# LE910_eval_0.net
KiCad netlist of a schematic drawn in EAGLE
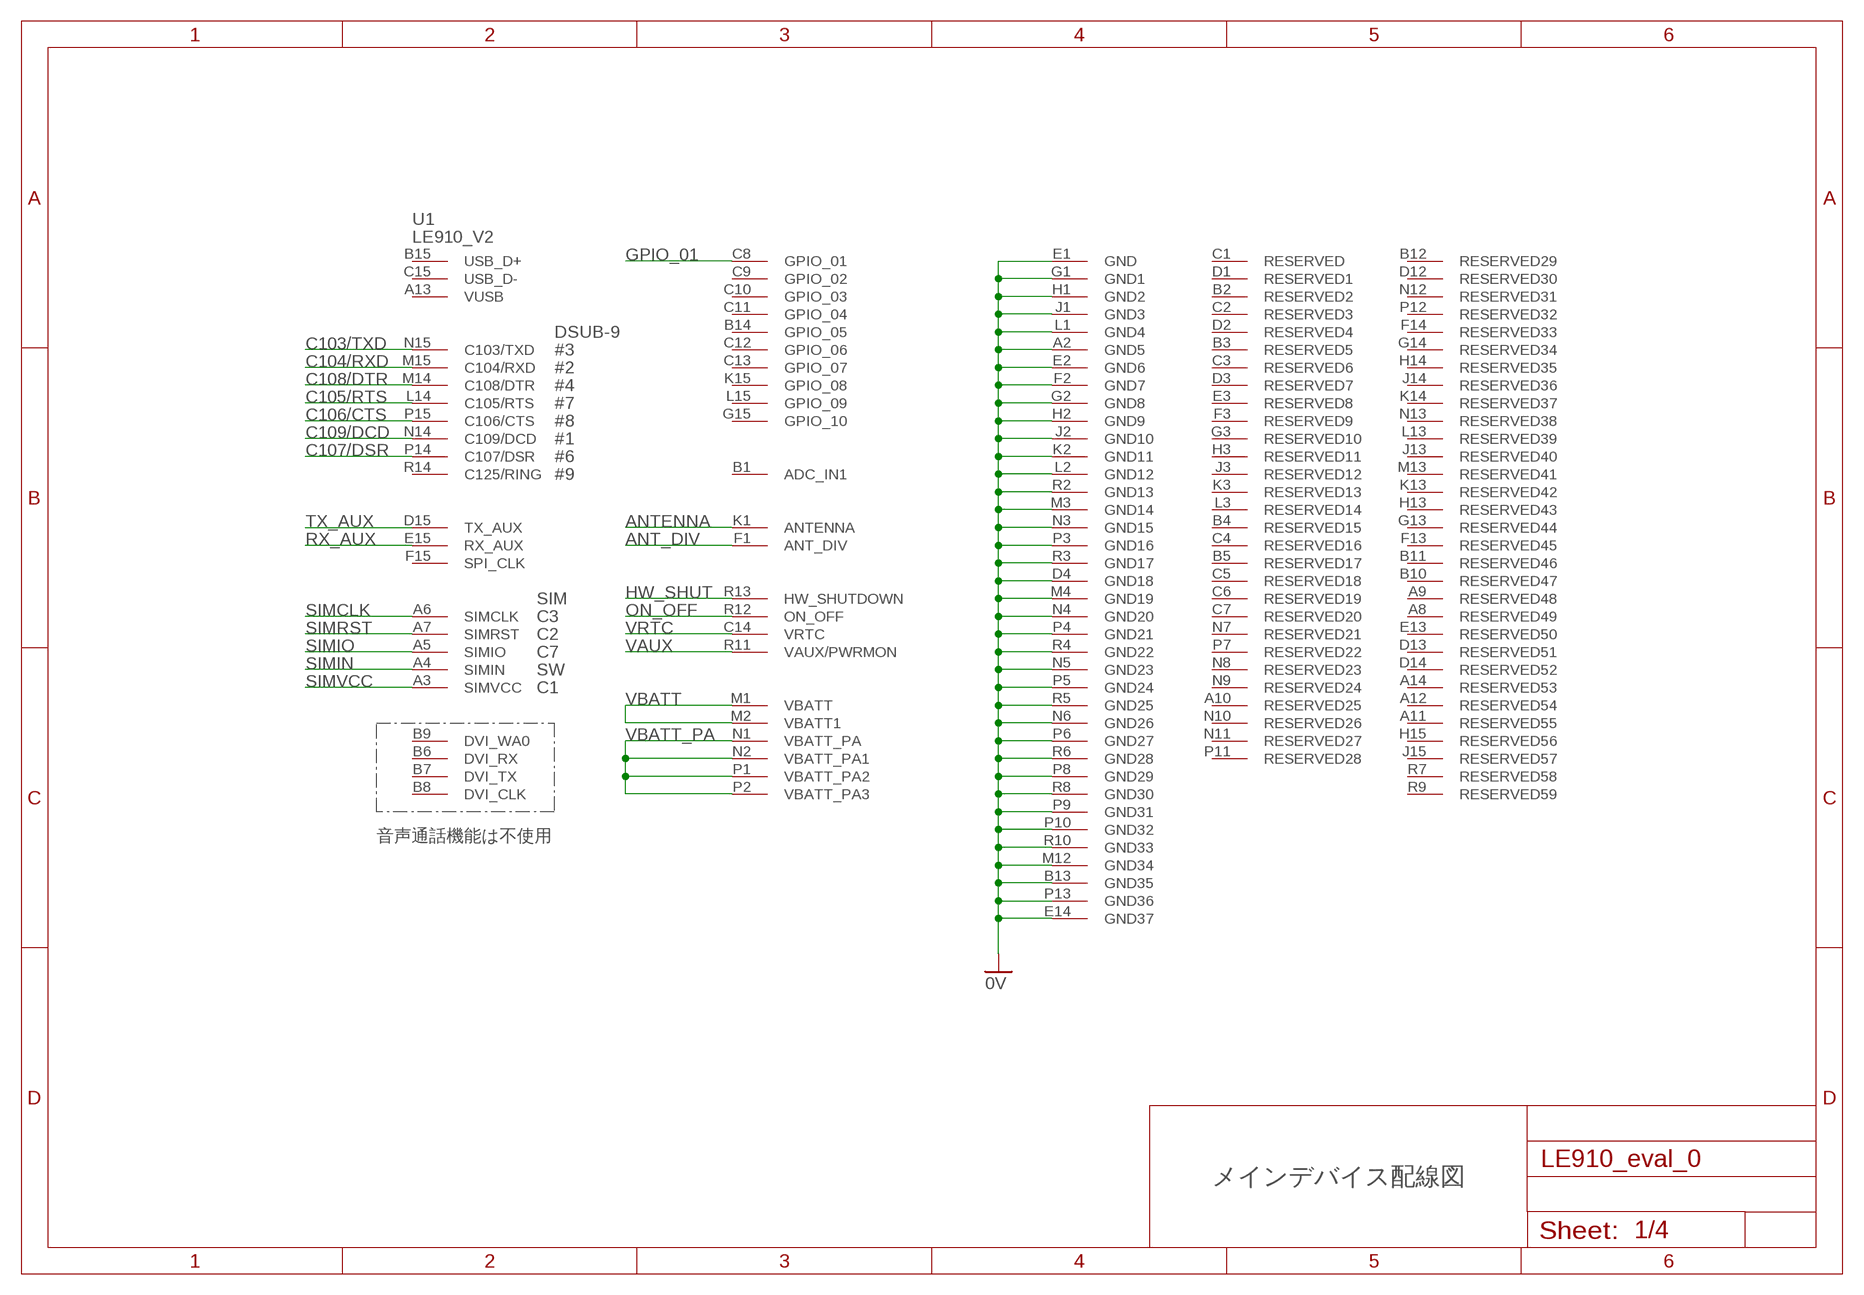
[diagram p0: schematic, sheet 1]
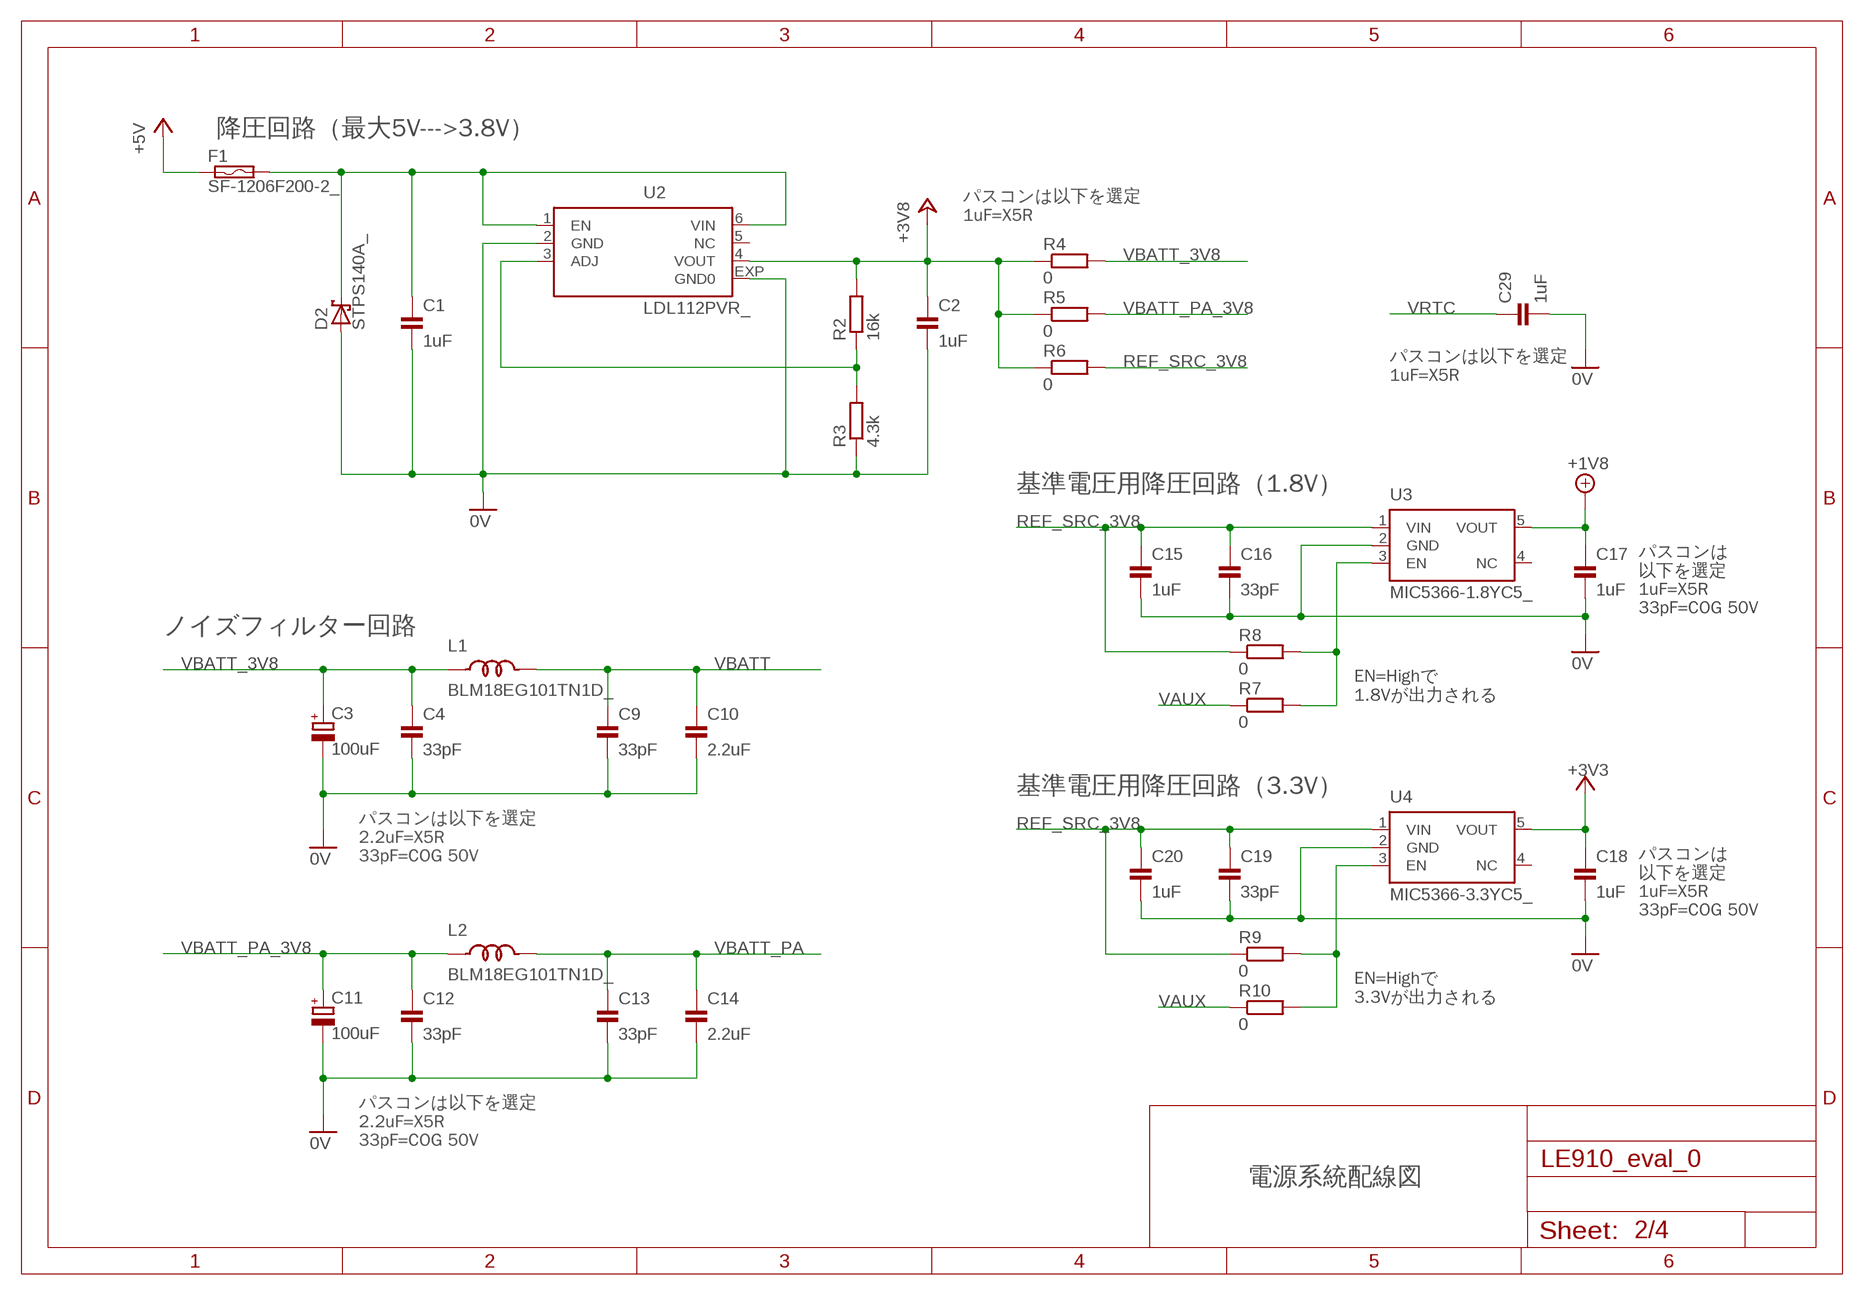
[diagram p1: schematic, sheet 2]
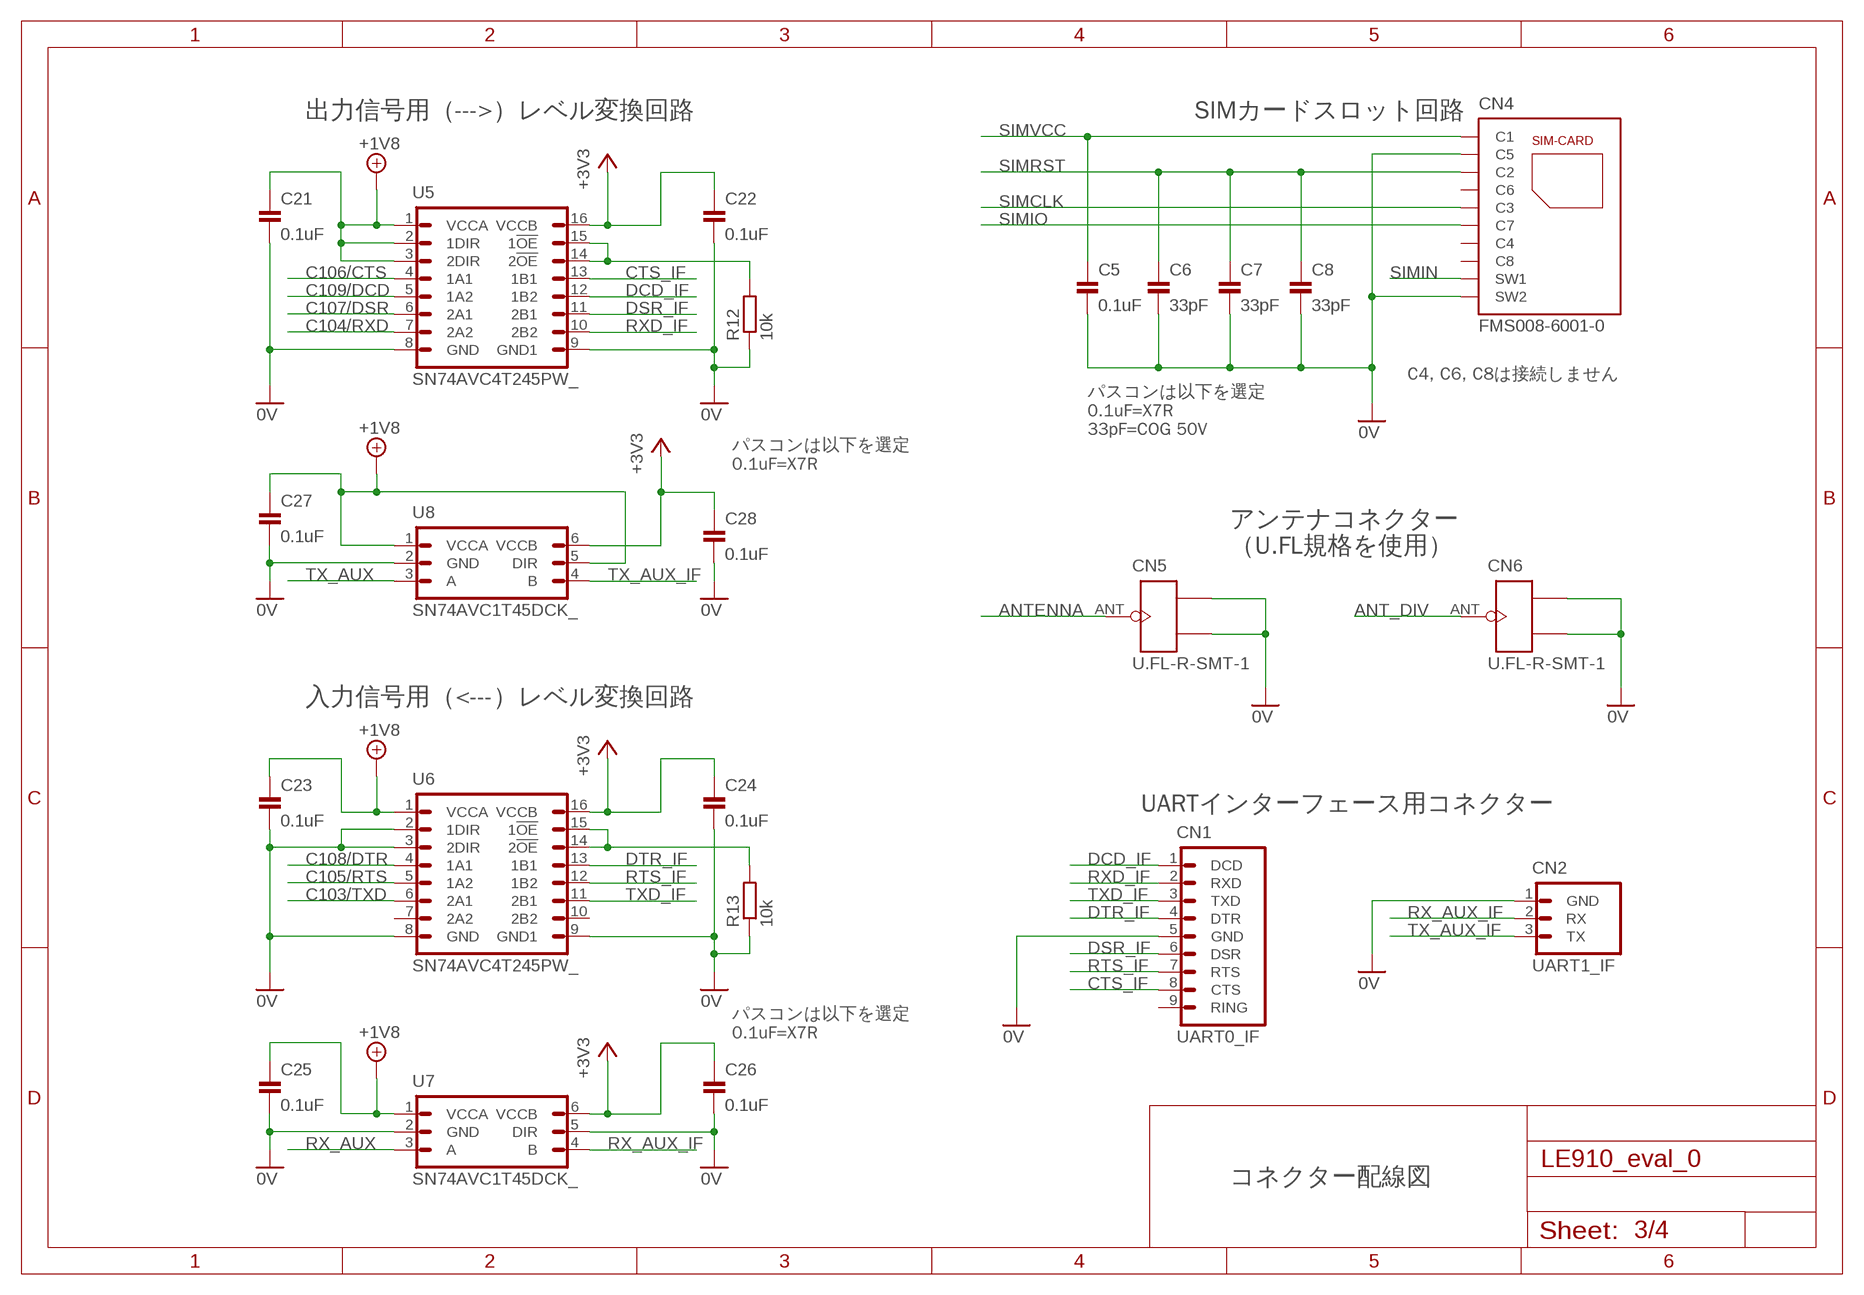
[diagram p2: schematic, sheet 3]
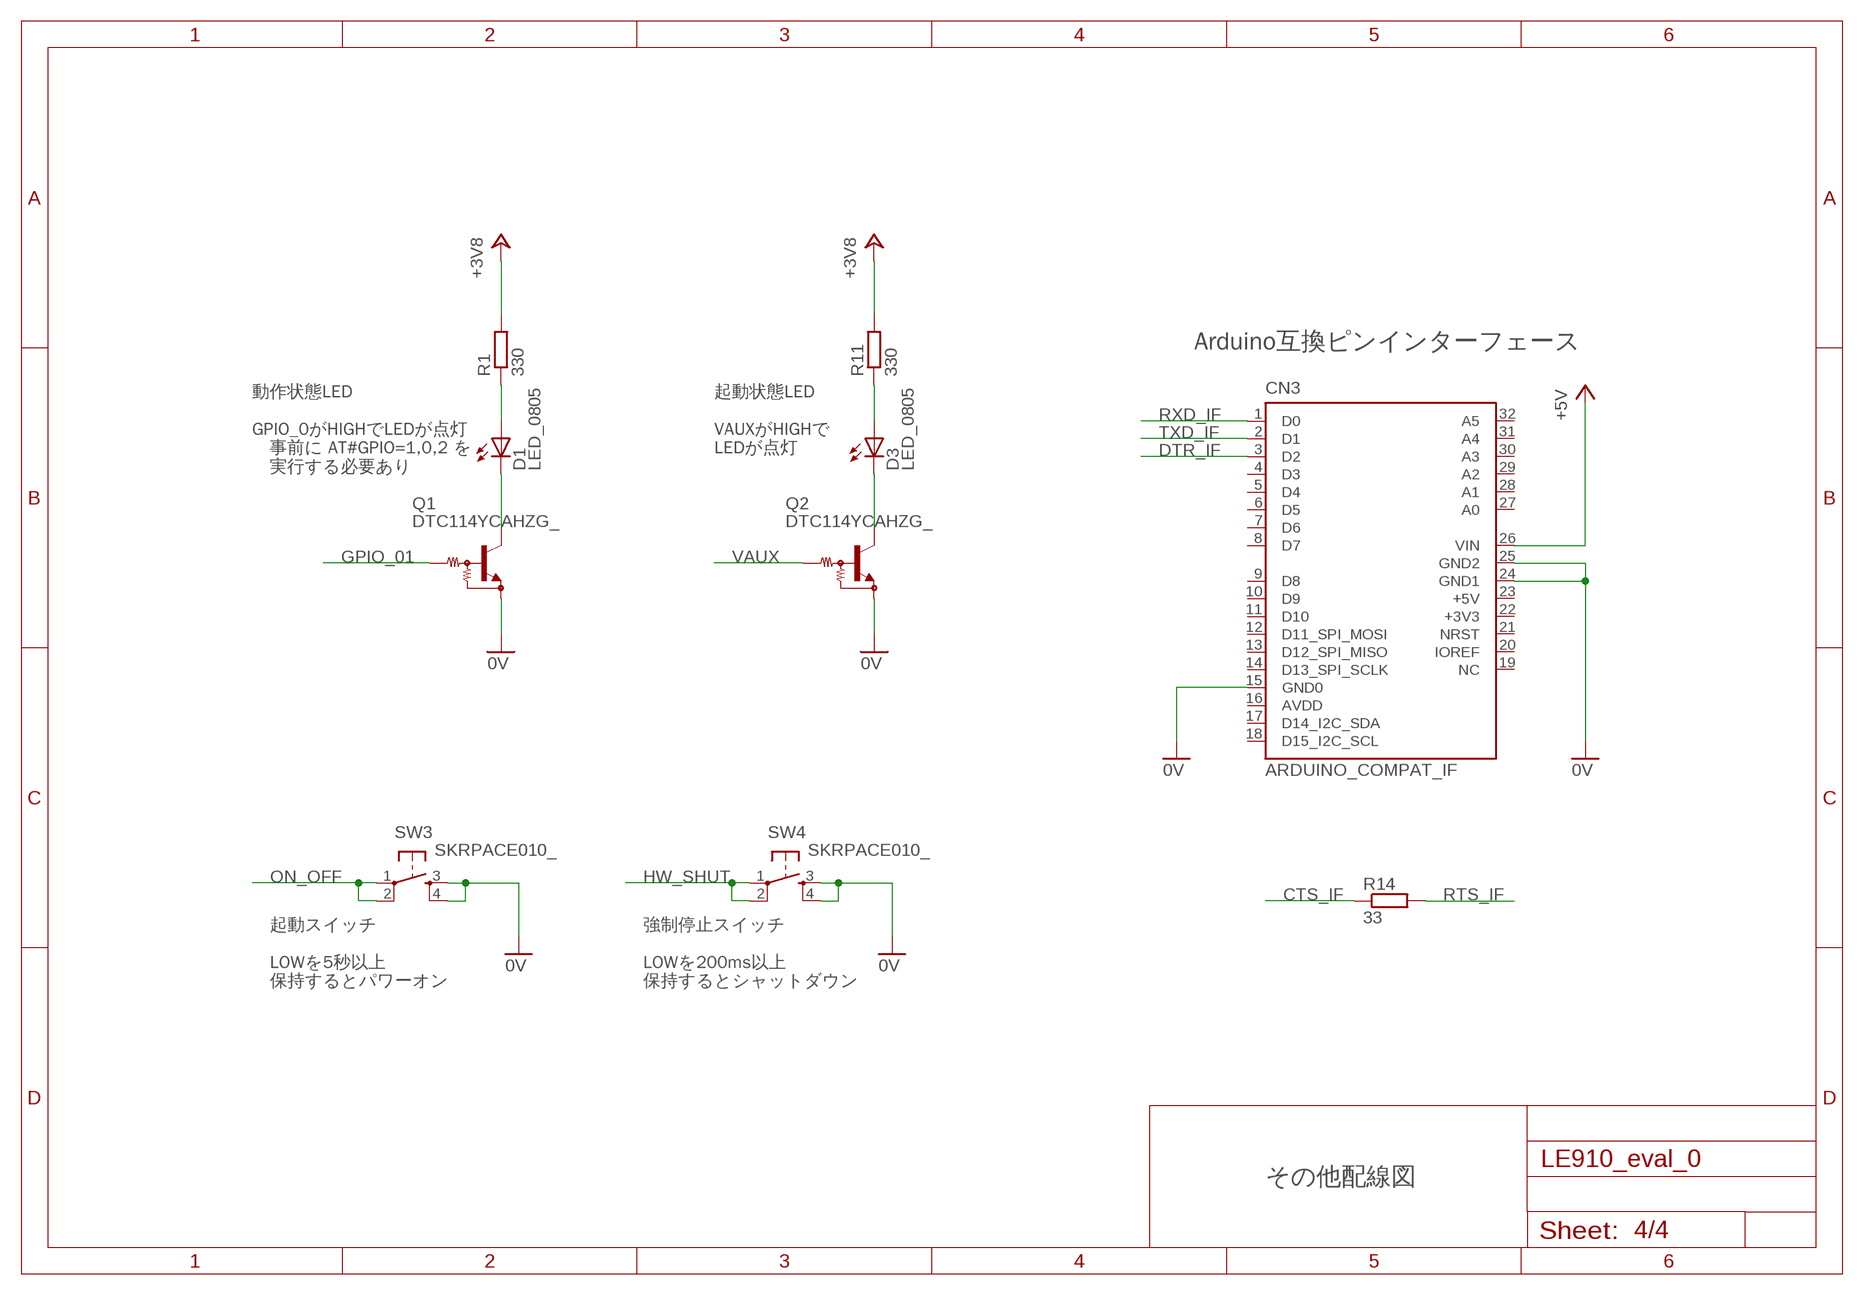
[diagram p3: schematic, sheet 4]

(export (version "E")
  (design (tool "Eeschema 10.0.6"))
  (components
    (comp (ref "CN3")
      (value "ARDUINO_COMPAT_IF")
      (footprint "eagle-import:ARDUINO_COMPAT_IF")
      (libsource (lib "eagle-import") (part "ARDUINO_COMPAT_IF"))
    )
    (comp (ref "D1")
      (value "LED_0805")
      (footprint "eagle-import:CHIPLED_0805")
      (libsource (lib "eagle-import") (part "LED_0805"))
    )
    (comp (ref "D3")
      (value "LED_0805")
      (footprint "eagle-import:CHIPLED_0805")
      (libsource (lib "eagle-import") (part "LED_0805"))
    )
    (comp (ref "Q1")
      (value "DTC114YCAHZG_")
      (footprint "eagle-import:SOT23_DEV")
      (libsource (lib "eagle-import") (part "DTC114YCAHZG_"))
    )
    (comp (ref "Q2")
      (value "DTC114YCAHZG_")
      (footprint "eagle-import:SOT23_DEV")
      (libsource (lib "eagle-import") (part "DTC114YCAHZG_"))
    )
    (comp (ref "R1")
      (value "330")
      (footprint "eagle-import:SMD_1608_DEV")
      (libsource (lib "eagle-import") (part "RESISTOR_0603_DEV"))
    )
    (comp (ref "R11")
      (value "330")
      (footprint "eagle-import:SMD_1608_DEV")
      (libsource (lib "eagle-import") (part "RESISTOR_0603_DEV"))
    )
    (comp (ref "R14")
      (value "33")
      (footprint "eagle-import:SMD_1608_DEV")
      (libsource (lib "eagle-import") (part "RESISTOR_0603_DEV"))
    )
    (comp (ref "SW3")
      (value "SKRPACE010_")
      (footprint "eagle-import:SKRPACE010_DEV")
      (libsource (lib "eagle-import") (part "SKRPACE010_"))
    )
    (comp (ref "SW4")
      (value "SKRPACE010_")
      (footprint "eagle-import:SKRPACE010_DEV")
      (libsource (lib "eagle-import") (part "SKRPACE010_"))
    )
    (comp (ref "C1")
      (value "1uF")
      (footprint "eagle-import:SMD_1608_DEV")
      (libsource (lib "eagle-import") (part "CAP_0603_DEV"))
    )
    (comp (ref "C2")
      (value "1uF")
      (footprint "eagle-import:SMD_1608_DEV")
      (libsource (lib "eagle-import") (part "CAP_0603_DEV"))
    )
    (comp (ref "C3")
      (value "100uF")
      (footprint "eagle-import:CT6032")
      (libsource (lib "eagle-import") (part "TPSW107K006R0150"))
    )
    (comp (ref "C4")
      (value "33pF")
      (footprint "eagle-import:SMD_1608_DEV")
      (libsource (lib "eagle-import") (part "CAP_0603_DEV"))
    )
    (comp (ref "C9")
      (value "33pF")
      (footprint "eagle-import:SMD_1608_DEV")
      (libsource (lib "eagle-import") (part "CAP_0603_DEV"))
    )
    (comp (ref "C10")
      (value "2.2uF")
      (footprint "eagle-import:SMD_1608_DEV")
      (libsource (lib "eagle-import") (part "CAP_0603_DEV"))
    )
    (comp (ref "C11")
      (value "100uF")
      (footprint "eagle-import:CT6032")
      (libsource (lib "eagle-import") (part "TPSW107K006R0150"))
    )
    (comp (ref "C12")
      (value "33pF")
      (footprint "eagle-import:SMD_1608_DEV")
      (libsource (lib "eagle-import") (part "CAP_0603_DEV"))
    )
    (comp (ref "C13")
      (value "33pF")
      (footprint "eagle-import:SMD_1608_DEV")
      (libsource (lib "eagle-import") (part "CAP_0603_DEV"))
    )
    (comp (ref "C14")
      (value "2.2uF")
      (footprint "eagle-import:SMD_1608_DEV")
      (libsource (lib "eagle-import") (part "CAP_0603_DEV"))
    )
    (comp (ref "C15")
      (value "1uF")
      (footprint "eagle-import:SMD_1608_DEV")
      (libsource (lib "eagle-import") (part "CAP_0603_DEV"))
    )
    (comp (ref "C16")
      (value "33pF")
      (footprint "eagle-import:SMD_1608_DEV")
      (libsource (lib "eagle-import") (part "CAP_0603_DEV"))
    )
    (comp (ref "C17")
      (value "1uF")
      (footprint "eagle-import:SMD_1608_DEV")
      (libsource (lib "eagle-import") (part "CAP_0603_DEV"))
    )
    (comp (ref "C18")
      (value "1uF")
      (footprint "eagle-import:SMD_1608_DEV")
      (libsource (lib "eagle-import") (part "CAP_0603_DEV"))
    )
    (comp (ref "C19")
      (value "33pF")
      (footprint "eagle-import:SMD_1608_DEV")
      (libsource (lib "eagle-import") (part "CAP_0603_DEV"))
    )
    (comp (ref "C20")
      (value "1uF")
      (footprint "eagle-import:SMD_1608_DEV")
      (libsource (lib "eagle-import") (part "CAP_0603_DEV"))
    )
    (comp (ref "C29")
      (value "1uF")
      (footprint "eagle-import:SMD_1608_DEV")
      (libsource (lib "eagle-import") (part "CAP_0603_DEV"))
    )
    (comp (ref "D2")
      (value "STPS140A_")
      (footprint "eagle-import:SMA_DEV")
      (libsource (lib "eagle-import") (part "STPS140A_"))
    )
    (comp (ref "F1")
      (value "SF-1206F200-2_")
      (footprint "eagle-import:SF-1206F_DEV")
      (libsource (lib "eagle-import") (part "SF-1206F200-2_"))
    )
    (comp (ref "L1")
      (value "BLM18EG101TN1D_")
      (footprint "eagle-import:SMD_1608_DEV")
      (libsource (lib "eagle-import") (part "BLM18EG101TN1D_"))
    )
    (comp (ref "L2")
      (value "BLM18EG101TN1D_")
      (footprint "eagle-import:SMD_1608_DEV")
      (libsource (lib "eagle-import") (part "BLM18EG101TN1D_"))
    )
    (comp (ref "R2")
      (value "16k")
      (footprint "eagle-import:SMD_1608_DEV")
      (libsource (lib "eagle-import") (part "RESISTOR_0603_DEV"))
    )
    (comp (ref "R3")
      (value "4.3k")
      (footprint "eagle-import:SMD_1608_DEV")
      (libsource (lib "eagle-import") (part "RESISTOR_0603_DEV"))
    )
    (comp (ref "R4")
      (value "0")
      (footprint "eagle-import:SMD_1608_DEV")
      (libsource (lib "eagle-import") (part "RESISTOR_0603_DEV"))
    )
    (comp (ref "R5")
      (value "0")
      (footprint "eagle-import:SMD_1608_DEV")
      (libsource (lib "eagle-import") (part "RESISTOR_0603_DEV"))
    )
    (comp (ref "R6")
      (value "0")
      (footprint "eagle-import:SMD_1608_DEV")
      (libsource (lib "eagle-import") (part "RESISTOR_0603_DEV"))
    )
    (comp (ref "R7")
      (value "0")
      (footprint "eagle-import:SMD_1608_DEV")
      (libsource (lib "eagle-import") (part "RESISTOR_0603_DEV"))
    )
    (comp (ref "R8")
      (value "0")
      (footprint "eagle-import:SMD_1608_DEV")
      (libsource (lib "eagle-import") (part "RESISTOR_0603_DEV"))
    )
    (comp (ref "R9")
      (value "0")
      (footprint "eagle-import:SMD_1608_DEV")
      (libsource (lib "eagle-import") (part "RESISTOR_0603_DEV"))
    )
    (comp (ref "R10")
      (value "0")
      (footprint "eagle-import:SMD_1608_DEV")
      (libsource (lib "eagle-import") (part "RESISTOR_0603_DEV"))
    )
    (comp (ref "U2")
      (value "LDL112PVR_")
      (footprint "eagle-import:DFN6-3X3_DEV")
      (libsource (lib "eagle-import") (part "LDL112PVR_"))
    )
    (comp (ref "U3")
      (value "MIC5366-1.8YC5_")
      (footprint "eagle-import:SC-70-5_DEV")
      (libsource (lib "eagle-import") (part "MIC5366-1.8YC5_"))
    )
    (comp (ref "U4")
      (value "MIC5366-3.3YC5_")
      (footprint "eagle-import:SC-70-5_DEV")
      (libsource (lib "eagle-import") (part "MIC5366-3.3YC5_"))
    )
    (comp (ref "U1")
      (value "LE910_V2")
      (footprint "eagle-import:LE910_V2")
      (libsource (lib "eagle-import") (part "LE910_V2"))
    )
    (comp (ref "C5")
      (value "0.1uF")
      (footprint "eagle-import:SMD_1608_DEV")
      (libsource (lib "eagle-import") (part "CAP_0603_DEV"))
    )
    (comp (ref "C6")
      (value "33pF")
      (footprint "eagle-import:SMD_1608_DEV")
      (libsource (lib "eagle-import") (part "CAP_0603_DEV"))
    )
    (comp (ref "C7")
      (value "33pF")
      (footprint "eagle-import:SMD_1608_DEV")
      (libsource (lib "eagle-import") (part "CAP_0603_DEV"))
    )
    (comp (ref "C8")
      (value "33pF")
      (footprint "eagle-import:SMD_1608_DEV")
      (libsource (lib "eagle-import") (part "CAP_0603_DEV"))
    )
    (comp (ref "C21")
      (value "0.1uF")
      (footprint "eagle-import:SMD_1608_DEV")
      (libsource (lib "eagle-import") (part "CAP_0603_DEV"))
    )
    (comp (ref "C22")
      (value "0.1uF")
      (footprint "eagle-import:SMD_1608_DEV")
      (libsource (lib "eagle-import") (part "CAP_0603_DEV"))
    )
    (comp (ref "C23")
      (value "0.1uF")
      (footprint "eagle-import:SMD_1608_DEV")
      (libsource (lib "eagle-import") (part "CAP_0603_DEV"))
    )
    (comp (ref "C24")
      (value "0.1uF")
      (footprint "eagle-import:SMD_1608_DEV")
      (libsource (lib "eagle-import") (part "CAP_0603_DEV"))
    )
    (comp (ref "C25")
      (value "0.1uF")
      (footprint "eagle-import:SMD_1608_DEV")
      (libsource (lib "eagle-import") (part "CAP_0603_DEV"))
    )
    (comp (ref "C26")
      (value "0.1uF")
      (footprint "eagle-import:SMD_1608_DEV")
      (libsource (lib "eagle-import") (part "CAP_0603_DEV"))
    )
    (comp (ref "C27")
      (value "0.1uF")
      (footprint "eagle-import:SMD_1608_DEV")
      (libsource (lib "eagle-import") (part "CAP_0603_DEV"))
    )
    (comp (ref "C28")
      (value "0.1uF")
      (footprint "eagle-import:SMD_1608_DEV")
      (libsource (lib "eagle-import") (part "CAP_0603_DEV"))
    )
    (comp (ref "CN1")
      (value "UART0_IF")
      (footprint "eagle-import:RS_232C_IF_9PIN")
      (libsource (lib "eagle-import") (part "RS_232C_IF"))
    )
    (comp (ref "CN2")
      (value "UART1_IF")
      (footprint "eagle-import:UART_IF_3PIN")
      (libsource (lib "eagle-import") (part "UART_IF"))
    )
    (comp (ref "CN4")
      (value "FMS008-6001-0")
      (footprint "eagle-import:FMS008-6001-0")
      (libsource (lib "eagle-import") (part "FMS008-6001-0"))
    )
    (comp (ref "CN5")
      (value "U.FL-R-SMT-1")
      (footprint "eagle-import:U.FL-R-SMT-1")
      (libsource (lib "eagle-import") (part "U.FL-R-SMT-1"))
    )
    (comp (ref "CN6")
      (value "U.FL-R-SMT-1")
      (footprint "eagle-import:U.FL-R-SMT-1")
      (libsource (lib "eagle-import") (part "U.FL-R-SMT-1"))
    )
    (comp (ref "R12")
      (value "10k")
      (footprint "eagle-import:SMD_1608_DEV")
      (libsource (lib "eagle-import") (part "RESISTOR_0603_DEV"))
    )
    (comp (ref "R13")
      (value "10k")
      (footprint "eagle-import:SMD_1608_DEV")
      (libsource (lib "eagle-import") (part "RESISTOR_0603_DEV"))
    )
    (comp (ref "U5")
      (value "SN74AVC4T245PW_")
      (footprint "eagle-import:TSSOP-16_DEV")
      (libsource (lib "eagle-import") (part "SN74AVC4T245PW_"))
    )
    (comp (ref "U6")
      (value "SN74AVC4T245PW_")
      (footprint "eagle-import:TSSOP-16_DEV")
      (libsource (lib "eagle-import") (part "SN74AVC4T245PW_"))
    )
    (comp (ref "U7")
      (value "SN74AVC1T45DCK_")
      (footprint "eagle-import:SC-70-6_DEV")
      (libsource (lib "eagle-import") (part "SN74AVC1T45DCK_"))
    )
    (comp (ref "U8")
      (value "SN74AVC1T45DCK_")
      (footprint "eagle-import:SC-70-6_DEV")
      (libsource (lib "eagle-import") (part "SN74AVC1T45DCK_"))
    )
  )
  (nets
    (net (code "1") (name "+1V8") (class "Default")
      (node (ref "C17") (pin "1") (pinfunction "1_1") (pintype "passive"))
      (node (ref "C21") (pin "1") (pinfunction "1_1") (pintype "passive"))
      (node (ref "C23") (pin "1") (pinfunction "1_1") (pintype "passive"))
      (node (ref "C25") (pin "1") (pinfunction "1_1") (pintype "passive"))
      (node (ref "C27") (pin "1") (pinfunction "1_1") (pintype "passive"))
      (node (ref "U3") (pin "5") (pinfunction "VOUT_5") (pintype "passive"))
      (node (ref "U5") (pin "1") (pinfunction "VCCA_1") (pintype "passive"))
      (node (ref "U5") (pin "2") (pinfunction "1DIR_2") (pintype "bidirectional"))
      (node (ref "U5") (pin "3") (pinfunction "2DIR_3") (pintype "bidirectional"))
      (node (ref "U6") (pin "1") (pinfunction "VCCA_1") (pintype "passive"))
      (node (ref "U7") (pin "1") (pinfunction "VCCA_1") (pintype "passive"))
      (node (ref "U8") (pin "1") (pinfunction "VCCA_1") (pintype "passive"))
      (node (ref "U8") (pin "5") (pinfunction "DIR_5") (pintype "bidirectional"))
    )
    (net (code "2") (name "+3V3") (class "Default")
      (node (ref "C18") (pin "1") (pinfunction "1_1") (pintype "passive"))
      (node (ref "C22") (pin "1") (pinfunction "1_1") (pintype "passive"))
      (node (ref "C24") (pin "1") (pinfunction "1_1") (pintype "passive"))
      (node (ref "C26") (pin "1") (pinfunction "1_1") (pintype "passive"))
      (node (ref "C28") (pin "1") (pinfunction "1_1") (pintype "passive"))
      (node (ref "U4") (pin "5") (pinfunction "VOUT_5") (pintype "passive"))
      (node (ref "U5") (pin "16") (pinfunction "VCCB_16") (pintype "passive"))
      (node (ref "U6") (pin "16") (pinfunction "VCCB_16") (pintype "passive"))
      (node (ref "U7") (pin "6") (pinfunction "VCCB_6") (pintype "passive"))
      (node (ref "U8") (pin "6") (pinfunction "VCCB_6") (pintype "passive"))
    )
    (net (code "3") (name "+3V8") (class "Default")
      (node (ref "C2") (pin "1") (pinfunction "1_1") (pintype "passive"))
      (node (ref "R1") (pin "2") (pinfunction "2_2") (pintype "passive"))
      (node (ref "R11") (pin "2") (pinfunction "2_2") (pintype "passive"))
      (node (ref "R2") (pin "2") (pinfunction "2_2") (pintype "passive"))
      (node (ref "R4") (pin "1") (pinfunction "1_1") (pintype "passive"))
      (node (ref "R5") (pin "1") (pinfunction "1_1") (pintype "passive"))
      (node (ref "R6") (pin "1") (pinfunction "1_1") (pintype "passive"))
      (node (ref "U2") (pin "4") (pinfunction "VOUT_4") (pintype "passive"))
    )
    (net (code "4") (name "+5V") (class "Default")
      (node (ref "CN3") (pin "26") (pinfunction "VIN_26") (pintype "passive"))
      (node (ref "F1") (pin "1") (pinfunction "1_1") (pintype "passive"))
    )
    (net (code "5") (name "0V") (class "Default")
      (node (ref "C1") (pin "2") (pinfunction "2_2") (pintype "passive"))
      (node (ref "C10") (pin "2") (pinfunction "2_2") (pintype "passive"))
      (node (ref "C11") (pin "-") (pinfunction "-_-") (pintype "passive"))
      (node (ref "C12") (pin "2") (pinfunction "2_2") (pintype "passive"))
      (node (ref "C13") (pin "2") (pinfunction "2_2") (pintype "passive"))
      (node (ref "C14") (pin "2") (pinfunction "2_2") (pintype "passive"))
      (node (ref "C15") (pin "2") (pinfunction "2_2") (pintype "passive"))
      (node (ref "C16") (pin "2") (pinfunction "2_2") (pintype "passive"))
      (node (ref "C17") (pin "2") (pinfunction "2_2") (pintype "passive"))
      (node (ref "C18") (pin "2") (pinfunction "2_2") (pintype "passive"))
      (node (ref "C19") (pin "2") (pinfunction "2_2") (pintype "passive"))
      (node (ref "C2") (pin "2") (pinfunction "2_2") (pintype "passive"))
      (node (ref "C20") (pin "2") (pinfunction "2_2") (pintype "passive"))
      (node (ref "C21") (pin "2") (pinfunction "2_2") (pintype "passive"))
      (node (ref "C22") (pin "2") (pinfunction "2_2") (pintype "passive"))
      (node (ref "C23") (pin "2") (pinfunction "2_2") (pintype "passive"))
      (node (ref "C24") (pin "2") (pinfunction "2_2") (pintype "passive"))
      (node (ref "C25") (pin "2") (pinfunction "2_2") (pintype "passive"))
      (node (ref "C26") (pin "2") (pinfunction "2_2") (pintype "passive"))
      (node (ref "C27") (pin "2") (pinfunction "2_2") (pintype "passive"))
      (node (ref "C28") (pin "2") (pinfunction "2_2") (pintype "passive"))
      (node (ref "C29") (pin "2") (pinfunction "2_2") (pintype "passive"))
      (node (ref "C3") (pin "-") (pinfunction "-_-") (pintype "passive"))
      (node (ref "C4") (pin "2") (pinfunction "2_2") (pintype "passive"))
      (node (ref "C5") (pin "2") (pinfunction "2_2") (pintype "passive"))
      (node (ref "C6") (pin "2") (pinfunction "2_2") (pintype "passive"))
      (node (ref "C7") (pin "2") (pinfunction "2_2") (pintype "passive"))
      (node (ref "C8") (pin "2") (pinfunction "2_2") (pintype "passive"))
      (node (ref "C9") (pin "2") (pinfunction "2_2") (pintype "passive"))
      (node (ref "CN1") (pin "5") (pinfunction "GND_5") (pintype "passive"))
      (node (ref "CN2") (pin "1") (pinfunction "GND_1") (pintype "passive"))
      (node (ref "CN3") (pin "15") (pinfunction "GND0_15") (pintype "passive"))
      (node (ref "CN3") (pin "24") (pinfunction "GND1_24") (pintype "passive"))
      (node (ref "CN3") (pin "25") (pinfunction "GND2_25") (pintype "passive"))
      (node (ref "CN4") (pin "C5") (pinfunction "C5_C5") (pintype "passive"))
      (node (ref "CN4") (pin "SW2") (pinfunction "SW2_SW2") (pintype "bidirectional"))
      (node (ref "CN5") (pin "GND1") (pinfunction "GND1_GND1") (pintype "passive"))
      (node (ref "CN5") (pin "GND2") (pinfunction "GND2_GND2") (pintype "passive"))
      (node (ref "CN6") (pin "GND1") (pinfunction "GND1_GND1") (pintype "passive"))
      (node (ref "CN6") (pin "GND2") (pinfunction "GND2_GND2") (pintype "passive"))
      (node (ref "D2") (pin "2") (pinfunction "A_2") (pintype "passive"))
      (node (ref "Q1") (pin "2") (pinfunction "E_2") (pintype "passive"))
      (node (ref "Q2") (pin "2") (pinfunction "E_2") (pintype "passive"))
      (node (ref "R12") (pin "1") (pinfunction "1_1") (pintype "passive"))
      (node (ref "R13") (pin "1") (pinfunction "1_1") (pintype "passive"))
      (node (ref "R3") (pin "1") (pinfunction "1_1") (pintype "passive"))
      (node (ref "SW3") (pin "3") (pinfunction "S_3") (pintype "passive"))
      (node (ref "SW3") (pin "4") (pinfunction "S1_4") (pintype "passive"))
      (node (ref "SW4") (pin "3") (pinfunction "S_3") (pintype "passive"))
      (node (ref "SW4") (pin "4") (pinfunction "S1_4") (pintype "passive"))
      (node (ref "U1") (pin "A2") (pinfunction "GND5_A2") (pintype "passive"))
      (node (ref "U1") (pin "B13") (pinfunction "GND35_B13") (pintype "passive"))
      (node (ref "U1") (pin "D4") (pinfunction "GND18_D4") (pintype "passive"))
      (node (ref "U1") (pin "E1") (pinfunction "GND_E1") (pintype "passive"))
      (node (ref "U1") (pin "E14") (pinfunction "GND37_E14") (pintype "passive"))
      (node (ref "U1") (pin "E2") (pinfunction "GND6_E2") (pintype "passive"))
      (node (ref "U1") (pin "F2") (pinfunction "GND7_F2") (pintype "passive"))
      (node (ref "U1") (pin "G1") (pinfunction "GND1_G1") (pintype "passive"))
      (node (ref "U1") (pin "G2") (pinfunction "GND8_G2") (pintype "passive"))
      (node (ref "U1") (pin "H1") (pinfunction "GND2_H1") (pintype "passive"))
      (node (ref "U1") (pin "H2") (pinfunction "GND9_H2") (pintype "passive"))
      (node (ref "U1") (pin "J1") (pinfunction "GND3_J1") (pintype "passive"))
      (node (ref "U1") (pin "J2") (pinfunction "GND10_J2") (pintype "passive"))
      (node (ref "U1") (pin "K2") (pinfunction "GND11_K2") (pintype "passive"))
      (node (ref "U1") (pin "L1") (pinfunction "GND4_L1") (pintype "passive"))
      (node (ref "U1") (pin "L2") (pinfunction "GND12_L2") (pintype "passive"))
      (node (ref "U1") (pin "M12") (pinfunction "GND34_M12") (pintype "passive"))
      (node (ref "U1") (pin "M3") (pinfunction "GND14_M3") (pintype "passive"))
      (node (ref "U1") (pin "M4") (pinfunction "GND19_M4") (pintype "passive"))
      (node (ref "U1") (pin "N3") (pinfunction "GND15_N3") (pintype "passive"))
      (node (ref "U1") (pin "N4") (pinfunction "GND20_N4") (pintype "passive"))
      (node (ref "U1") (pin "N5") (pinfunction "GND23_N5") (pintype "passive"))
      (node (ref "U1") (pin "N6") (pinfunction "GND26_N6") (pintype "passive"))
      (node (ref "U1") (pin "P10") (pinfunction "GND32_P10") (pintype "passive"))
      (node (ref "U1") (pin "P13") (pinfunction "GND36_P13") (pintype "passive"))
      (node (ref "U1") (pin "P3") (pinfunction "GND16_P3") (pintype "passive"))
      (node (ref "U1") (pin "P4") (pinfunction "GND21_P4") (pintype "passive"))
      (node (ref "U1") (pin "P5") (pinfunction "GND24_P5") (pintype "passive"))
      (node (ref "U1") (pin "P6") (pinfunction "GND27_P6") (pintype "passive"))
      (node (ref "U1") (pin "P8") (pinfunction "GND29_P8") (pintype "passive"))
      (node (ref "U1") (pin "P9") (pinfunction "GND31_P9") (pintype "passive"))
      (node (ref "U1") (pin "R10") (pinfunction "GND33_R10") (pintype "passive"))
      (node (ref "U1") (pin "R2") (pinfunction "GND13_R2") (pintype "passive"))
      (node (ref "U1") (pin "R3") (pinfunction "GND17_R3") (pintype "passive"))
      (node (ref "U1") (pin "R4") (pinfunction "GND22_R4") (pintype "passive"))
      (node (ref "U1") (pin "R5") (pinfunction "GND25_R5") (pintype "passive"))
      (node (ref "U1") (pin "R6") (pinfunction "GND28_R6") (pintype "passive"))
      (node (ref "U1") (pin "R8") (pinfunction "GND30_R8") (pintype "passive"))
      (node (ref "U2") (pin "2") (pinfunction "GND_2") (pintype "passive"))
      (node (ref "U2") (pin "EXP") (pinfunction "GND0_EXP") (pintype "passive"))
      (node (ref "U3") (pin "2") (pinfunction "GND_2") (pintype "passive"))
      (node (ref "U4") (pin "2") (pinfunction "GND_2") (pintype "passive"))
      (node (ref "U5") (pin "8") (pinfunction "GND_8") (pintype "passive"))
      (node (ref "U5") (pin "9") (pinfunction "GND1_9") (pintype "passive"))
      (node (ref "U6") (pin "2") (pinfunction "1DIR_2") (pintype "bidirectional"))
      (node (ref "U6") (pin "3") (pinfunction "2DIR_3") (pintype "bidirectional"))
      (node (ref "U6") (pin "8") (pinfunction "GND_8") (pintype "passive"))
      (node (ref "U6") (pin "9") (pinfunction "GND1_9") (pintype "passive"))
      (node (ref "U7") (pin "2") (pinfunction "GND_2") (pintype "passive"))
      (node (ref "U7") (pin "5") (pinfunction "DIR_5") (pintype "bidirectional"))
      (node (ref "U8") (pin "2") (pinfunction "GND_2") (pintype "passive"))
    )
    (net (code "6") (name "ANTENNA") (class "Default")
      (node (ref "CN5") (pin "ANT") (pinfunction "ANT_ANT") (pintype "passive"))
      (node (ref "U1") (pin "K1") (pinfunction "ANTENNA_K1") (pintype "bidirectional"))
    )
    (net (code "7") (name "ANT_DIV") (class "Default")
      (node (ref "CN6") (pin "ANT") (pinfunction "ANT_ANT") (pintype "passive"))
      (node (ref "U1") (pin "F1") (pinfunction "ANT_DIV_F1") (pintype "bidirectional"))
    )
    (net (code "8") (name "C103{slash}TXD") (class "Default")
      (node (ref "U1") (pin "N15") (pinfunction "C103/TXD_N15") (pintype "bidirectional"))
      (node (ref "U6") (pin "6") (pinfunction "2A1_6") (pintype "bidirectional"))
    )
    (net (code "9") (name "C104{slash}RXD") (class "Default")
      (node (ref "U1") (pin "M15") (pinfunction "C104/RXD_M15") (pintype "bidirectional"))
      (node (ref "U5") (pin "7") (pinfunction "2A2_7") (pintype "bidirectional"))
    )
    (net (code "10") (name "C105{slash}RTS") (class "Default")
      (node (ref "U1") (pin "L14") (pinfunction "C105/RTS_L14") (pintype "bidirectional"))
      (node (ref "U6") (pin "5") (pinfunction "1A2_5") (pintype "bidirectional"))
    )
    (net (code "11") (name "C106{slash}CTS") (class "Default")
      (node (ref "U1") (pin "P15") (pinfunction "C106/CTS_P15") (pintype "bidirectional"))
      (node (ref "U5") (pin "4") (pinfunction "1A1_4") (pintype "bidirectional"))
    )
    (net (code "12") (name "C107{slash}DSR") (class "Default")
      (node (ref "U1") (pin "P14") (pinfunction "C107/DSR_P14") (pintype "bidirectional"))
      (node (ref "U5") (pin "6") (pinfunction "2A1_6") (pintype "bidirectional"))
    )
    (net (code "13") (name "C108{slash}DTR") (class "Default")
      (node (ref "U1") (pin "M14") (pinfunction "C108/DTR_M14") (pintype "bidirectional"))
      (node (ref "U6") (pin "4") (pinfunction "1A1_4") (pintype "bidirectional"))
    )
    (net (code "14") (name "C109{slash}DCD") (class "Default")
      (node (ref "U1") (pin "N14") (pinfunction "C109/DCD_N14") (pintype "bidirectional"))
      (node (ref "U5") (pin "5") (pinfunction "1A2_5") (pintype "bidirectional"))
    )
    (net (code "15") (name "CTS_IF") (class "Default")
      (node (ref "CN1") (pin "8") (pinfunction "CTS_8") (pintype "bidirectional"))
      (node (ref "R14") (pin "1") (pinfunction "1_1") (pintype "passive"))
      (node (ref "U5") (pin "13") (pinfunction "1B1_13") (pintype "bidirectional"))
    )
    (net (code "16") (name "DCD_IF") (class "Default")
      (node (ref "CN1") (pin "1") (pinfunction "DCD_1") (pintype "bidirectional"))
      (node (ref "U5") (pin "12") (pinfunction "1B2_12") (pintype "bidirectional"))
    )
    (net (code "17") (name "DSR_IF") (class "Default")
      (node (ref "CN1") (pin "6") (pinfunction "DSR_6") (pintype "bidirectional"))
      (node (ref "U5") (pin "11") (pinfunction "2B1_11") (pintype "bidirectional"))
    )
    (net (code "18") (name "DTR_IF") (class "Default")
      (node (ref "CN1") (pin "4") (pinfunction "DTR_4") (pintype "bidirectional"))
      (node (ref "CN3") (pin "3") (pinfunction "D2_3") (pintype "bidirectional"))
      (node (ref "U6") (pin "13") (pinfunction "1B1_13") (pintype "bidirectional"))
    )
    (net (code "19") (name "GPIO_01") (class "Default")
      (node (ref "Q1") (pin "1") (pinfunction "B_1") (pintype "passive"))
      (node (ref "U1") (pin "C8") (pinfunction "GPIO_01_C8") (pintype "bidirectional"))
    )
    (net (code "20") (name "HW_SHUT") (class "Default")
      (node (ref "SW4") (pin "1") (pinfunction "P_1") (pintype "passive"))
      (node (ref "SW4") (pin "2") (pinfunction "P1_2") (pintype "passive"))
      (node (ref "U1") (pin "R13") (pinfunction "HW_SHUTDOWN_R13") (pintype "bidirectional"))
    )
    (net (code "21") (name "Net-(D1-PadA)") (class "Default")
      (node (ref "D1") (pin "A") (pinfunction "A_A") (pintype "passive"))
      (node (ref "R1") (pin "1") (pinfunction "1_1") (pintype "passive"))
    )
    (net (code "22") (name "Net-(D2-C)") (class "Default")
      (node (ref "C1") (pin "1") (pinfunction "1_1") (pintype "passive"))
      (node (ref "D2") (pin "1") (pinfunction "C_1") (pintype "passive"))
      (node (ref "F1") (pin "2") (pinfunction "2_2") (pintype "passive"))
      (node (ref "U2") (pin "1") (pinfunction "EN_1") (pintype "bidirectional"))
      (node (ref "U2") (pin "6") (pinfunction "VIN_6") (pintype "passive"))
    )
    (net (code "23") (name "Net-(D3-PadA)") (class "Default")
      (node (ref "D3") (pin "A") (pinfunction "A_A") (pintype "passive"))
      (node (ref "R11") (pin "1") (pinfunction "1_1") (pintype "passive"))
    )
    (net (code "24") (name "Net-(Q1-C)") (class "Default")
      (node (ref "D1") (pin "C") (pinfunction "C_C") (pintype "passive"))
      (node (ref "Q1") (pin "3") (pinfunction "C_3") (pintype "passive"))
    )
    (net (code "25") (name "Net-(Q2-C)") (class "Default")
      (node (ref "D3") (pin "C") (pinfunction "C_C") (pintype "passive"))
      (node (ref "Q2") (pin "3") (pinfunction "C_3") (pintype "passive"))
    )
    (net (code "26") (name "Net-(U2-ADJ)") (class "Default")
      (node (ref "R2") (pin "1") (pinfunction "1_1") (pintype "passive"))
      (node (ref "R3") (pin "2") (pinfunction "2_2") (pintype "passive"))
      (node (ref "U2") (pin "3") (pinfunction "ADJ_3") (pintype "bidirectional"))
    )
    (net (code "27") (name "Net-(U3-EN)") (class "Default")
      (node (ref "R7") (pin "2") (pinfunction "2_2") (pintype "passive"))
      (node (ref "R8") (pin "2") (pinfunction "2_2") (pintype "passive"))
      (node (ref "U3") (pin "3") (pinfunction "EN_3") (pintype "bidirectional"))
    )
    (net (code "28") (name "Net-(U4-EN)") (class "Default")
      (node (ref "R10") (pin "2") (pinfunction "2_2") (pintype "passive"))
      (node (ref "R9") (pin "2") (pinfunction "2_2") (pintype "passive"))
      (node (ref "U4") (pin "3") (pinfunction "EN_3") (pintype "bidirectional"))
    )
    (net (code "29") (name "Net-(U5-1~{OE})") (class "Default")
      (node (ref "R12") (pin "2") (pinfunction "2_2") (pintype "passive"))
      (node (ref "U5") (pin "14") (pinfunction "2~{OE}_14") (pintype "bidirectional"))
      (node (ref "U5") (pin "15") (pinfunction "1~{OE}_15") (pintype "bidirectional"))
    )
    (net (code "30") (name "Net-(U6-1~{OE})") (class "Default")
      (node (ref "R13") (pin "2") (pinfunction "2_2") (pintype "passive"))
      (node (ref "U6") (pin "14") (pinfunction "2~{OE}_14") (pintype "bidirectional"))
      (node (ref "U6") (pin "15") (pinfunction "1~{OE}_15") (pintype "bidirectional"))
    )
    (net (code "31") (name "ON_OFF") (class "Default")
      (node (ref "SW3") (pin "1") (pinfunction "P_1") (pintype "passive"))
      (node (ref "SW3") (pin "2") (pinfunction "P1_2") (pintype "passive"))
      (node (ref "U1") (pin "R12") (pinfunction "ON_OFF_R12") (pintype "bidirectional"))
    )
    (net (code "32") (name "REF_SRC_3V8") (class "Default")
      (node (ref "C15") (pin "1") (pinfunction "1_1") (pintype "passive"))
      (node (ref "C16") (pin "1") (pinfunction "1_1") (pintype "passive"))
      (node (ref "C19") (pin "1") (pinfunction "1_1") (pintype "passive"))
      (node (ref "C20") (pin "1") (pinfunction "1_1") (pintype "passive"))
      (node (ref "R6") (pin "2") (pinfunction "2_2") (pintype "passive"))
      (node (ref "R8") (pin "1") (pinfunction "1_1") (pintype "passive"))
      (node (ref "R9") (pin "1") (pinfunction "1_1") (pintype "passive"))
      (node (ref "U3") (pin "1") (pinfunction "VIN_1") (pintype "passive"))
      (node (ref "U4") (pin "1") (pinfunction "VIN_1") (pintype "passive"))
    )
    (net (code "33") (name "RTS_IF") (class "Default")
      (node (ref "CN1") (pin "7") (pinfunction "RTS_7") (pintype "bidirectional"))
      (node (ref "R14") (pin "2") (pinfunction "2_2") (pintype "passive"))
      (node (ref "U6") (pin "12") (pinfunction "1B2_12") (pintype "bidirectional"))
    )
    (net (code "34") (name "RXD_IF") (class "Default")
      (node (ref "CN1") (pin "2") (pinfunction "RXD_2") (pintype "bidirectional"))
      (node (ref "CN3") (pin "1") (pinfunction "D0_1") (pintype "bidirectional"))
      (node (ref "U5") (pin "10") (pinfunction "2B2_10") (pintype "bidirectional"))
    )
    (net (code "35") (name "RX_AUX") (class "Default")
      (node (ref "U1") (pin "E15") (pinfunction "RX_AUX_E15") (pintype "bidirectional"))
      (node (ref "U7") (pin "3") (pinfunction "A_3") (pintype "bidirectional"))
    )
    (net (code "36") (name "RX_AUX_IF") (class "Default")
      (node (ref "CN2") (pin "2") (pinfunction "RX_2") (pintype "bidirectional"))
      (node (ref "U7") (pin "4") (pinfunction "B_4") (pintype "bidirectional"))
    )
    (net (code "37") (name "SIMCLK") (class "Default")
      (node (ref "CN4") (pin "C3") (pinfunction "C3_C3") (pintype "bidirectional"))
      (node (ref "U1") (pin "A6") (pinfunction "SIMCLK_A6") (pintype "bidirectional"))
    )
    (net (code "38") (name "SIMIN") (class "Default")
      (node (ref "CN4") (pin "SW1") (pinfunction "SW1_SW1") (pintype "bidirectional"))
      (node (ref "U1") (pin "A4") (pinfunction "SIMIN_A4") (pintype "bidirectional"))
    )
    (net (code "39") (name "SIMIO") (class "Default")
      (node (ref "CN4") (pin "C7") (pinfunction "C7_C7") (pintype "bidirectional"))
      (node (ref "U1") (pin "A5") (pinfunction "SIMIO_A5") (pintype "bidirectional"))
    )
    (net (code "40") (name "SIMRST") (class "Default")
      (node (ref "C6") (pin "1") (pinfunction "1_1") (pintype "passive"))
      (node (ref "C7") (pin "1") (pinfunction "1_1") (pintype "passive"))
      (node (ref "C8") (pin "1") (pinfunction "1_1") (pintype "passive"))
      (node (ref "CN4") (pin "C2") (pinfunction "C2_C2") (pintype "bidirectional"))
      (node (ref "U1") (pin "A7") (pinfunction "SIMRST_A7") (pintype "bidirectional"))
    )
    (net (code "41") (name "SIMVCC") (class "Default")
      (node (ref "C5") (pin "1") (pinfunction "1_1") (pintype "passive"))
      (node (ref "CN4") (pin "C1") (pinfunction "C1_C1") (pintype "passive"))
      (node (ref "U1") (pin "A3") (pinfunction "SIMVCC_A3") (pintype "passive"))
    )
    (net (code "42") (name "TXD_IF") (class "Default")
      (node (ref "CN1") (pin "3") (pinfunction "TXD_3") (pintype "bidirectional"))
      (node (ref "CN3") (pin "2") (pinfunction "D1_2") (pintype "bidirectional"))
      (node (ref "U6") (pin "11") (pinfunction "2B1_11") (pintype "bidirectional"))
    )
    (net (code "43") (name "TX_AUX") (class "Default")
      (node (ref "U1") (pin "D15") (pinfunction "TX_AUX_D15") (pintype "bidirectional"))
      (node (ref "U8") (pin "3") (pinfunction "A_3") (pintype "bidirectional"))
    )
    (net (code "44") (name "TX_AUX_IF") (class "Default")
      (node (ref "CN2") (pin "3") (pinfunction "TX_3") (pintype "bidirectional"))
      (node (ref "U8") (pin "4") (pinfunction "B_4") (pintype "bidirectional"))
    )
    (net (code "45") (name "VAUX") (class "Default")
      (node (ref "Q2") (pin "1") (pinfunction "B_1") (pintype "passive"))
      (node (ref "R10") (pin "1") (pinfunction "1_1") (pintype "passive"))
      (node (ref "R7") (pin "1") (pinfunction "1_1") (pintype "passive"))
      (node (ref "U1") (pin "R11") (pinfunction "VAUX/PWRMON_R11") (pintype "bidirectional"))
    )
    (net (code "46") (name "VBATT") (class "Default")
      (node (ref "C10") (pin "1") (pinfunction "1_1") (pintype "passive"))
      (node (ref "C9") (pin "1") (pinfunction "1_1") (pintype "passive"))
      (node (ref "L1") (pin "2") (pinfunction "2_2") (pintype "passive"))
      (node (ref "U1") (pin "M1") (pinfunction "VBATT_M1") (pintype "passive"))
      (node (ref "U1") (pin "M2") (pinfunction "VBATT1_M2") (pintype "passive"))
    )
    (net (code "47") (name "VBATT_3V8") (class "Default")
      (node (ref "C3") (pin "+") (pinfunction "+_+") (pintype "passive"))
      (node (ref "C4") (pin "1") (pinfunction "1_1") (pintype "passive"))
      (node (ref "L1") (pin "1") (pinfunction "1_1") (pintype "passive"))
      (node (ref "R4") (pin "2") (pinfunction "2_2") (pintype "passive"))
    )
    (net (code "48") (name "VBATT_PA") (class "Default")
      (node (ref "C13") (pin "1") (pinfunction "1_1") (pintype "passive"))
      (node (ref "C14") (pin "1") (pinfunction "1_1") (pintype "passive"))
      (node (ref "L2") (pin "2") (pinfunction "2_2") (pintype "passive"))
      (node (ref "U1") (pin "N1") (pinfunction "VBATT_PA_N1") (pintype "passive"))
      (node (ref "U1") (pin "N2") (pinfunction "VBATT_PA1_N2") (pintype "passive"))
      (node (ref "U1") (pin "P1") (pinfunction "VBATT_PA2_P1") (pintype "passive"))
      (node (ref "U1") (pin "P2") (pinfunction "VBATT_PA3_P2") (pintype "passive"))
    )
    (net (code "49") (name "VBATT_PA_3V8") (class "Default")
      (node (ref "C11") (pin "+") (pinfunction "+_+") (pintype "passive"))
      (node (ref "C12") (pin "1") (pinfunction "1_1") (pintype "passive"))
      (node (ref "L2") (pin "1") (pinfunction "1_1") (pintype "passive"))
      (node (ref "R5") (pin "2") (pinfunction "2_2") (pintype "passive"))
    )
    (net (code "50") (name "VRTC") (class "Default")
      (node (ref "C29") (pin "1") (pinfunction "1_1") (pintype "passive"))
      (node (ref "U1") (pin "C14") (pinfunction "VRTC_C14") (pintype "bidirectional"))
    )
    (net (code "51") (name "unconnected-(CN1-RING-Pad9)") (class "Default")
      (node (ref "CN1") (pin "9") (pinfunction "RING_9") (pintype "bidirectional"))
    )
    (net (code "52") (name "unconnected-(CN3-+3V3-Pad22)") (class "Default")
      (node (ref "CN3") (pin "22") (pinfunction "+3V3_22") (pintype "passive"))
    )
    (net (code "53") (name "unconnected-(CN3-+5V-Pad23)") (class "Default")
      (node (ref "CN3") (pin "23") (pinfunction "+5V_23") (pintype "passive"))
    )
    (net (code "54") (name "unconnected-(CN3-A0-Pad27)") (class "Default")
      (node (ref "CN3") (pin "27") (pinfunction "A0_27") (pintype "bidirectional"))
    )
    (net (code "55") (name "unconnected-(CN3-A1-Pad28)") (class "Default")
      (node (ref "CN3") (pin "28") (pinfunction "A1_28") (pintype "bidirectional"))
    )
    (net (code "56") (name "unconnected-(CN3-A2-Pad29)") (class "Default")
      (node (ref "CN3") (pin "29") (pinfunction "A2_29") (pintype "bidirectional"))
    )
    (net (code "57") (name "unconnected-(CN3-A3-Pad30)") (class "Default")
      (node (ref "CN3") (pin "30") (pinfunction "A3_30") (pintype "bidirectional"))
    )
    (net (code "58") (name "unconnected-(CN3-A4-Pad31)") (class "Default")
      (node (ref "CN3") (pin "31") (pinfunction "A4_31") (pintype "bidirectional"))
    )
    (net (code "59") (name "unconnected-(CN3-A5-Pad32)") (class "Default")
      (node (ref "CN3") (pin "32") (pinfunction "A5_32") (pintype "bidirectional"))
    )
    (net (code "60") (name "unconnected-(CN3-AVDD-Pad16)") (class "Default")
      (node (ref "CN3") (pin "16") (pinfunction "AVDD_16") (pintype "passive"))
    )
    (net (code "61") (name "unconnected-(CN3-D3-Pad4)") (class "Default")
      (node (ref "CN3") (pin "4") (pinfunction "D3_4") (pintype "bidirectional"))
    )
    (net (code "62") (name "unconnected-(CN3-D4-Pad5)") (class "Default")
      (node (ref "CN3") (pin "5") (pinfunction "D4_5") (pintype "bidirectional"))
    )
    (net (code "63") (name "unconnected-(CN3-D5-Pad6)") (class "Default")
      (node (ref "CN3") (pin "6") (pinfunction "D5_6") (pintype "bidirectional"))
    )
    (net (code "64") (name "unconnected-(CN3-D6-Pad7)") (class "Default")
      (node (ref "CN3") (pin "7") (pinfunction "D6_7") (pintype "bidirectional"))
    )
    (net (code "65") (name "unconnected-(CN3-D7-Pad8)") (class "Default")
      (node (ref "CN3") (pin "8") (pinfunction "D7_8") (pintype "bidirectional"))
    )
    (net (code "66") (name "unconnected-(CN3-D8-Pad9)") (class "Default")
      (node (ref "CN3") (pin "9") (pinfunction "D8_9") (pintype "bidirectional"))
    )
    (net (code "67") (name "unconnected-(CN3-D9-Pad10)") (class "Default")
      (node (ref "CN3") (pin "10") (pinfunction "D9_10") (pintype "bidirectional"))
    )
    (net (code "68") (name "unconnected-(CN3-D10-Pad11)") (class "Default")
      (node (ref "CN3") (pin "11") (pinfunction "D10_11") (pintype "bidirectional"))
    )
    (net (code "69") (name "unconnected-(CN3-D11_SPI_MOSI-Pad12)") (class "Default")
      (node (ref "CN3") (pin "12") (pinfunction "D11_SPI_MOSI_12") (pintype "bidirectional"))
    )
    (net (code "70") (name "unconnected-(CN3-D12_SPI_MISO-Pad13)") (class "Default")
      (node (ref "CN3") (pin "13") (pinfunction "D12_SPI_MISO_13") (pintype "bidirectional"))
    )
    (net (code "71") (name "unconnected-(CN3-D13_SPI_SCLK-Pad14)") (class "Default")
      (node (ref "CN3") (pin "14") (pinfunction "D13_SPI_SCLK_14") (pintype "bidirectional"))
    )
    (net (code "72") (name "unconnected-(CN3-D14_I2C_SDA-Pad17)") (class "Default")
      (node (ref "CN3") (pin "17") (pinfunction "D14_I2C_SDA_17") (pintype "passive"))
    )
    (net (code "73") (name "unconnected-(CN3-D15_I2C_SCL-Pad18)") (class "Default")
      (node (ref "CN3") (pin "18") (pinfunction "D15_I2C_SCL_18") (pintype "passive"))
    )
    (net (code "74") (name "unconnected-(CN3-IOREF-Pad20)") (class "Default")
      (node (ref "CN3") (pin "20") (pinfunction "IOREF_20") (pintype "bidirectional"))
    )
    (net (code "75") (name "unconnected-(CN3-NC-Pad19)") (class "Default")
      (node (ref "CN3") (pin "19") (pinfunction "NC_19") (pintype "no_connect"))
    )
    (net (code "76") (name "unconnected-(CN3-NRST-Pad21)") (class "Default")
      (node (ref "CN3") (pin "21") (pinfunction "NRST_21") (pintype "bidirectional"))
    )
    (net (code "77") (name "unconnected-(CN4-PadC4)") (class "Default")
      (node (ref "CN4") (pin "C4") (pinfunction "C4_C4") (pintype "bidirectional"))
    )
    (net (code "78") (name "unconnected-(CN4-PadC6)") (class "Default")
      (node (ref "CN4") (pin "C6") (pinfunction "C6_C6") (pintype "passive"))
    )
    (net (code "79") (name "unconnected-(CN4-PadC8)") (class "Default")
      (node (ref "CN4") (pin "C8") (pinfunction "C8_C8") (pintype "bidirectional"))
    )
    (net (code "80") (name "unconnected-(U1-ADC_IN1-PadB1)") (class "Default")
      (node (ref "U1") (pin "B1") (pinfunction "ADC_IN1_B1") (pintype "bidirectional"))
    )
    (net (code "81") (name "unconnected-(U1-C125{slash}RING-PadR14)") (class "Default")
      (node (ref "U1") (pin "R14") (pinfunction "C125/RING_R14") (pintype "bidirectional"))
    )
    (net (code "82") (name "unconnected-(U1-DVI_CLK-PadB8)") (class "Default")
      (node (ref "U1") (pin "B8") (pinfunction "DVI_CLK_B8") (pintype "bidirectional"))
    )
    (net (code "83") (name "unconnected-(U1-DVI_RX-PadB6)") (class "Default")
      (node (ref "U1") (pin "B6") (pinfunction "DVI_RX_B6") (pintype "bidirectional"))
    )
    (net (code "84") (name "unconnected-(U1-DVI_TX-PadB7)") (class "Default")
      (node (ref "U1") (pin "B7") (pinfunction "DVI_TX_B7") (pintype "bidirectional"))
    )
    (net (code "85") (name "unconnected-(U1-DVI_WA0-PadB9)") (class "Default")
      (node (ref "U1") (pin "B9") (pinfunction "DVI_WA0_B9") (pintype "bidirectional"))
    )
    (net (code "86") (name "unconnected-(U1-GPIO_02-PadC9)") (class "Default")
      (node (ref "U1") (pin "C9") (pinfunction "GPIO_02_C9") (pintype "bidirectional"))
    )
    (net (code "87") (name "unconnected-(U1-GPIO_03-PadC10)") (class "Default")
      (node (ref "U1") (pin "C10") (pinfunction "GPIO_03_C10") (pintype "bidirectional"))
    )
    (net (code "88") (name "unconnected-(U1-GPIO_04-PadC11)") (class "Default")
      (node (ref "U1") (pin "C11") (pinfunction "GPIO_04_C11") (pintype "bidirectional"))
    )
    (net (code "89") (name "unconnected-(U1-GPIO_05-PadB14)") (class "Default")
      (node (ref "U1") (pin "B14") (pinfunction "GPIO_05_B14") (pintype "bidirectional"))
    )
    (net (code "90") (name "unconnected-(U1-GPIO_06-PadC12)") (class "Default")
      (node (ref "U1") (pin "C12") (pinfunction "GPIO_06_C12") (pintype "bidirectional"))
    )
    (net (code "91") (name "unconnected-(U1-GPIO_07-PadC13)") (class "Default")
      (node (ref "U1") (pin "C13") (pinfunction "GPIO_07_C13") (pintype "bidirectional"))
    )
    (net (code "92") (name "unconnected-(U1-GPIO_08-PadK15)") (class "Default")
      (node (ref "U1") (pin "K15") (pinfunction "GPIO_08_K15") (pintype "bidirectional"))
    )
    (net (code "93") (name "unconnected-(U1-GPIO_09-PadL15)") (class "Default")
      (node (ref "U1") (pin "L15") (pinfunction "GPIO_09_L15") (pintype "bidirectional"))
    )
    (net (code "94") (name "unconnected-(U1-GPIO_10-PadG15)") (class "Default")
      (node (ref "U1") (pin "G15") (pinfunction "GPIO_10_G15") (pintype "bidirectional"))
    )
    (net (code "95") (name "unconnected-(U1-RESERVED-PadC1)") (class "Default")
      (node (ref "U1") (pin "C1") (pinfunction "RESERVED_C1") (pintype "no_connect"))
    )
    (net (code "96") (name "unconnected-(U1-RESERVED1-PadD1)") (class "Default")
      (node (ref "U1") (pin "D1") (pinfunction "RESERVED1_D1") (pintype "no_connect"))
    )
    (net (code "97") (name "unconnected-(U1-RESERVED2-PadB2)") (class "Default")
      (node (ref "U1") (pin "B2") (pinfunction "RESERVED2_B2") (pintype "no_connect"))
    )
    (net (code "98") (name "unconnected-(U1-RESERVED3-PadC2)") (class "Default")
      (node (ref "U1") (pin "C2") (pinfunction "RESERVED3_C2") (pintype "no_connect"))
    )
    (net (code "99") (name "unconnected-(U1-RESERVED4-PadD2)") (class "Default")
      (node (ref "U1") (pin "D2") (pinfunction "RESERVED4_D2") (pintype "no_connect"))
    )
    (net (code "100") (name "unconnected-(U1-RESERVED5-PadB3)") (class "Default")
      (node (ref "U1") (pin "B3") (pinfunction "RESERVED5_B3") (pintype "no_connect"))
    )
    (net (code "101") (name "unconnected-(U1-RESERVED6-PadC3)") (class "Default")
      (node (ref "U1") (pin "C3") (pinfunction "RESERVED6_C3") (pintype "no_connect"))
    )
    (net (code "102") (name "unconnected-(U1-RESERVED7-PadD3)") (class "Default")
      (node (ref "U1") (pin "D3") (pinfunction "RESERVED7_D3") (pintype "no_connect"))
    )
    (net (code "103") (name "unconnected-(U1-RESERVED8-PadE3)") (class "Default")
      (node (ref "U1") (pin "E3") (pinfunction "RESERVED8_E3") (pintype "no_connect"))
    )
    (net (code "104") (name "unconnected-(U1-RESERVED9-PadF3)") (class "Default")
      (node (ref "U1") (pin "F3") (pinfunction "RESERVED9_F3") (pintype "no_connect"))
    )
    (net (code "105") (name "unconnected-(U1-RESERVED10-PadG3)") (class "Default")
      (node (ref "U1") (pin "G3") (pinfunction "RESERVED10_G3") (pintype "no_connect"))
    )
    (net (code "106") (name "unconnected-(U1-RESERVED11-PadH3)") (class "Default")
      (node (ref "U1") (pin "H3") (pinfunction "RESERVED11_H3") (pintype "no_connect"))
    )
    (net (code "107") (name "unconnected-(U1-RESERVED12-PadJ3)") (class "Default")
      (node (ref "U1") (pin "J3") (pinfunction "RESERVED12_J3") (pintype "no_connect"))
    )
    (net (code "108") (name "unconnected-(U1-RESERVED13-PadK3)") (class "Default")
      (node (ref "U1") (pin "K3") (pinfunction "RESERVED13_K3") (pintype "no_connect"))
    )
    (net (code "109") (name "unconnected-(U1-RESERVED14-PadL3)") (class "Default")
      (node (ref "U1") (pin "L3") (pinfunction "RESERVED14_L3") (pintype "no_connect"))
    )
    (net (code "110") (name "unconnected-(U1-RESERVED15-PadB4)") (class "Default")
      (node (ref "U1") (pin "B4") (pinfunction "RESERVED15_B4") (pintype "no_connect"))
    )
    (net (code "111") (name "unconnected-(U1-RESERVED16-PadC4)") (class "Default")
      (node (ref "U1") (pin "C4") (pinfunction "RESERVED16_C4") (pintype "no_connect"))
    )
    (net (code "112") (name "unconnected-(U1-RESERVED17-PadB5)") (class "Default")
      (node (ref "U1") (pin "B5") (pinfunction "RESERVED17_B5") (pintype "no_connect"))
    )
    (net (code "113") (name "unconnected-(U1-RESERVED18-PadC5)") (class "Default")
      (node (ref "U1") (pin "C5") (pinfunction "RESERVED18_C5") (pintype "no_connect"))
    )
    (net (code "114") (name "unconnected-(U1-RESERVED19-PadC6)") (class "Default")
      (node (ref "U1") (pin "C6") (pinfunction "RESERVED19_C6") (pintype "no_connect"))
    )
    (net (code "115") (name "unconnected-(U1-RESERVED20-PadC7)") (class "Default")
      (node (ref "U1") (pin "C7") (pinfunction "RESERVED20_C7") (pintype "no_connect"))
    )
    (net (code "116") (name "unconnected-(U1-RESERVED21-PadN7)") (class "Default")
      (node (ref "U1") (pin "N7") (pinfunction "RESERVED21_N7") (pintype "no_connect"))
    )
    (net (code "117") (name "unconnected-(U1-RESERVED22-PadP7)") (class "Default")
      (node (ref "U1") (pin "P7") (pinfunction "RESERVED22_P7") (pintype "no_connect"))
    )
    (net (code "118") (name "unconnected-(U1-RESERVED23-PadN8)") (class "Default")
      (node (ref "U1") (pin "N8") (pinfunction "RESERVED23_N8") (pintype "no_connect"))
    )
    (net (code "119") (name "unconnected-(U1-RESERVED24-PadN9)") (class "Default")
      (node (ref "U1") (pin "N9") (pinfunction "RESERVED24_N9") (pintype "no_connect"))
    )
    (net (code "120") (name "unconnected-(U1-RESERVED25-PadA10)") (class "Default")
      (node (ref "U1") (pin "A10") (pinfunction "RESERVED25_A10") (pintype "no_connect"))
    )
    (net (code "121") (name "unconnected-(U1-RESERVED26-PadN10)") (class "Default")
      (node (ref "U1") (pin "N10") (pinfunction "RESERVED26_N10") (pintype "no_connect"))
    )
    (net (code "122") (name "unconnected-(U1-RESERVED27-PadN11)") (class "Default")
      (node (ref "U1") (pin "N11") (pinfunction "RESERVED27_N11") (pintype "no_connect"))
    )
    (net (code "123") (name "unconnected-(U1-RESERVED28-PadP11)") (class "Default")
      (node (ref "U1") (pin "P11") (pinfunction "RESERVED28_P11") (pintype "no_connect"))
    )
    (net (code "124") (name "unconnected-(U1-RESERVED29-PadB12)") (class "Default")
      (node (ref "U1") (pin "B12") (pinfunction "RESERVED29_B12") (pintype "no_connect"))
    )
    (net (code "125") (name "unconnected-(U1-RESERVED30-PadD12)") (class "Default")
      (node (ref "U1") (pin "D12") (pinfunction "RESERVED30_D12") (pintype "no_connect"))
    )
    (net (code "126") (name "unconnected-(U1-RESERVED31-PadN12)") (class "Default")
      (node (ref "U1") (pin "N12") (pinfunction "RESERVED31_N12") (pintype "no_connect"))
    )
    (net (code "127") (name "unconnected-(U1-RESERVED32-PadP12)") (class "Default")
      (node (ref "U1") (pin "P12") (pinfunction "RESERVED32_P12") (pintype "no_connect"))
    )
    (net (code "128") (name "unconnected-(U1-RESERVED33-PadF14)") (class "Default")
      (node (ref "U1") (pin "F14") (pinfunction "RESERVED33_F14") (pintype "no_connect"))
    )
    (net (code "129") (name "unconnected-(U1-RESERVED34-PadG14)") (class "Default")
      (node (ref "U1") (pin "G14") (pinfunction "RESERVED34_G14") (pintype "no_connect"))
    )
    (net (code "130") (name "unconnected-(U1-RESERVED35-PadH14)") (class "Default")
      (node (ref "U1") (pin "H14") (pinfunction "RESERVED35_H14") (pintype "no_connect"))
    )
    (net (code "131") (name "unconnected-(U1-RESERVED36-PadJ14)") (class "Default")
      (node (ref "U1") (pin "J14") (pinfunction "RESERVED36_J14") (pintype "no_connect"))
    )
    (net (code "132") (name "unconnected-(U1-RESERVED37-PadK14)") (class "Default")
      (node (ref "U1") (pin "K14") (pinfunction "RESERVED37_K14") (pintype "no_connect"))
    )
    (net (code "133") (name "unconnected-(U1-RESERVED38-PadN13)") (class "Default")
      (node (ref "U1") (pin "N13") (pinfunction "RESERVED38_N13") (pintype "no_connect"))
    )
    (net (code "134") (name "unconnected-(U1-RESERVED39-PadL13)") (class "Default")
      (node (ref "U1") (pin "L13") (pinfunction "RESERVED39_L13") (pintype "no_connect"))
    )
    (net (code "135") (name "unconnected-(U1-RESERVED40-PadJ13)") (class "Default")
      (node (ref "U1") (pin "J13") (pinfunction "RESERVED40_J13") (pintype "no_connect"))
    )
    (net (code "136") (name "unconnected-(U1-RESERVED41-PadM13)") (class "Default")
      (node (ref "U1") (pin "M13") (pinfunction "RESERVED41_M13") (pintype "no_connect"))
    )
    (net (code "137") (name "unconnected-(U1-RESERVED42-PadK13)") (class "Default")
      (node (ref "U1") (pin "K13") (pinfunction "RESERVED42_K13") (pintype "no_connect"))
    )
    (net (code "138") (name "unconnected-(U1-RESERVED43-PadH13)") (class "Default")
      (node (ref "U1") (pin "H13") (pinfunction "RESERVED43_H13") (pintype "no_connect"))
    )
    (net (code "139") (name "unconnected-(U1-RESERVED44-PadG13)") (class "Default")
      (node (ref "U1") (pin "G13") (pinfunction "RESERVED44_G13") (pintype "no_connect"))
    )
    (net (code "140") (name "unconnected-(U1-RESERVED45-PadF13)") (class "Default")
      (node (ref "U1") (pin "F13") (pinfunction "RESERVED45_F13") (pintype "no_connect"))
    )
    (net (code "141") (name "unconnected-(U1-RESERVED46-PadB11)") (class "Default")
      (node (ref "U1") (pin "B11") (pinfunction "RESERVED46_B11") (pintype "no_connect"))
    )
    (net (code "142") (name "unconnected-(U1-RESERVED47-PadB10)") (class "Default")
      (node (ref "U1") (pin "B10") (pinfunction "RESERVED47_B10") (pintype "no_connect"))
    )
    (net (code "143") (name "unconnected-(U1-RESERVED48-PadA9)") (class "Default")
      (node (ref "U1") (pin "A9") (pinfunction "RESERVED48_A9") (pintype "no_connect"))
    )
    (net (code "144") (name "unconnected-(U1-RESERVED49-PadA8)") (class "Default")
      (node (ref "U1") (pin "A8") (pinfunction "RESERVED49_A8") (pintype "no_connect"))
    )
    (net (code "145") (name "unconnected-(U1-RESERVED50-PadE13)") (class "Default")
      (node (ref "U1") (pin "E13") (pinfunction "RESERVED50_E13") (pintype "no_connect"))
    )
    (net (code "146") (name "unconnected-(U1-RESERVED51-PadD13)") (class "Default")
      (node (ref "U1") (pin "D13") (pinfunction "RESERVED51_D13") (pintype "no_connect"))
    )
    (net (code "147") (name "unconnected-(U1-RESERVED52-PadD14)") (class "Default")
      (node (ref "U1") (pin "D14") (pinfunction "RESERVED52_D14") (pintype "no_connect"))
    )
    (net (code "148") (name "unconnected-(U1-RESERVED53-PadA14)") (class "Default")
      (node (ref "U1") (pin "A14") (pinfunction "RESERVED53_A14") (pintype "no_connect"))
    )
    (net (code "149") (name "unconnected-(U1-RESERVED54-PadA12)") (class "Default")
      (node (ref "U1") (pin "A12") (pinfunction "RESERVED54_A12") (pintype "no_connect"))
    )
    (net (code "150") (name "unconnected-(U1-RESERVED55-PadA11)") (class "Default")
      (node (ref "U1") (pin "A11") (pinfunction "RESERVED55_A11") (pintype "no_connect"))
    )
    (net (code "151") (name "unconnected-(U1-RESERVED56-PadH15)") (class "Default")
      (node (ref "U1") (pin "H15") (pinfunction "RESERVED56_H15") (pintype "no_connect"))
    )
    (net (code "152") (name "unconnected-(U1-RESERVED57-PadJ15)") (class "Default")
      (node (ref "U1") (pin "J15") (pinfunction "RESERVED57_J15") (pintype "no_connect"))
    )
    (net (code "153") (name "unconnected-(U1-RESERVED58-PadR7)") (class "Default")
      (node (ref "U1") (pin "R7") (pinfunction "RESERVED58_R7") (pintype "no_connect"))
    )
    (net (code "154") (name "unconnected-(U1-RESERVED59-PadR9)") (class "Default")
      (node (ref "U1") (pin "R9") (pinfunction "RESERVED59_R9") (pintype "no_connect"))
    )
    (net (code "155") (name "unconnected-(U1-SPI_CLK-PadF15)") (class "Default")
      (node (ref "U1") (pin "F15") (pinfunction "SPI_CLK_F15") (pintype "bidirectional"))
    )
    (net (code "156") (name "unconnected-(U1-USB_D+-PadB15)") (class "Default")
      (node (ref "U1") (pin "B15") (pinfunction "USB_D+_B15") (pintype "bidirectional"))
    )
    (net (code "157") (name "unconnected-(U1-USB_D--PadC15)") (class "Default")
      (node (ref "U1") (pin "C15") (pinfunction "USB_D-_C15") (pintype "bidirectional"))
    )
    (net (code "158") (name "unconnected-(U1-VUSB-PadA13)") (class "Default")
      (node (ref "U1") (pin "A13") (pinfunction "VUSB_A13") (pintype "bidirectional"))
    )
    (net (code "159") (name "unconnected-(U2-NC-Pad5)") (class "Default")
      (node (ref "U2") (pin "5") (pinfunction "NC_5") (pintype "no_connect"))
    )
    (net (code "160") (name "unconnected-(U3-NC-Pad4)") (class "Default")
      (node (ref "U3") (pin "4") (pinfunction "NC_4") (pintype "no_connect"))
    )
    (net (code "161") (name "unconnected-(U4-NC-Pad4)") (class "Default")
      (node (ref "U4") (pin "4") (pinfunction "NC_4") (pintype "no_connect"))
    )
    (net (code "162") (name "unconnected-(U6-2A2-Pad7)") (class "Default")
      (node (ref "U6") (pin "7") (pinfunction "2A2_7") (pintype "bidirectional"))
    )
    (net (code "163") (name "unconnected-(U6-2B2-Pad10)") (class "Default")
      (node (ref "U6") (pin "10") (pinfunction "2B2_10") (pintype "bidirectional"))
    )
  )
)
